# Tele.net
KiCad netlist of a schematic drawn in Altium Designer
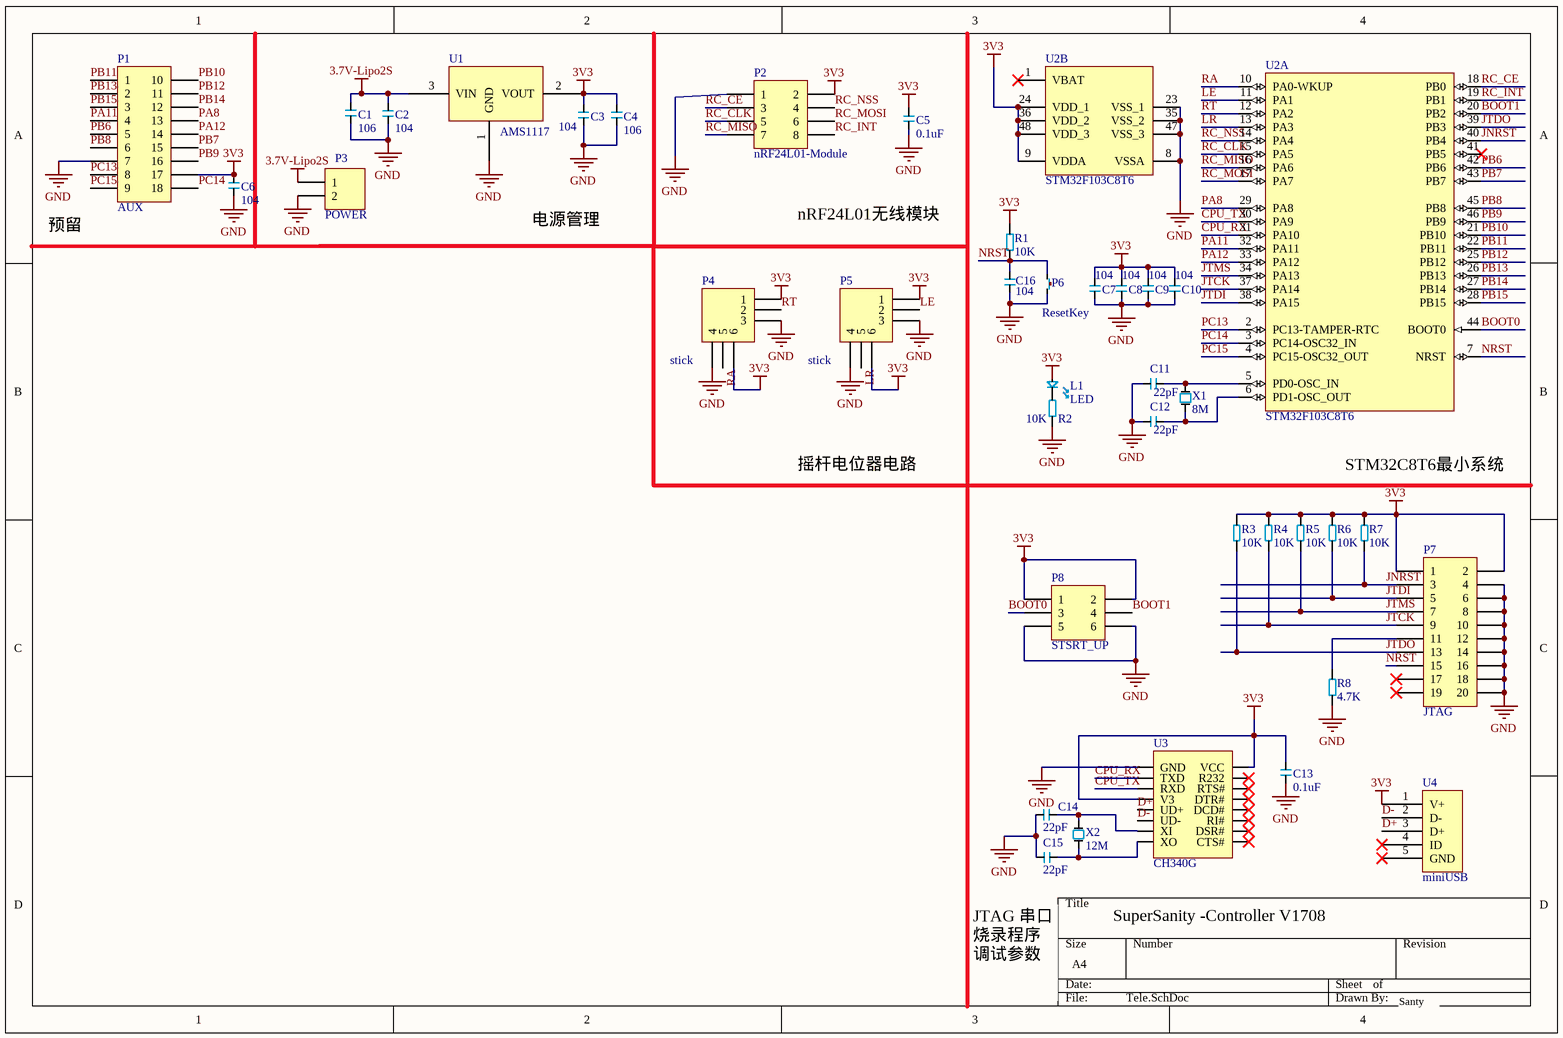
[diagram p0: Tele.SchDoc]

(export (version "E")
  (design (tool "Eeschema 10.0.6"))
  (components
    (comp (ref "C1") (value "106") (footprint "LC-0402") (libsource (lib "0402") (part "Cap-0402")))
    (comp (ref "C2") (value "104") (footprint "LC-0402") (libsource (lib "0402") (part "Cap-0402")))
    (comp (ref "C3") (value "104") (footprint "LC-0402") (libsource (lib "0402") (part "Cap-0402")))
    (comp (ref "C4") (value "106") (footprint "LC-0402") (libsource (lib "0402") (part "Cap-0402")))
    (comp (ref "C5") (value "0.1uF") (footprint "LC-0402") (libsource (lib "0402") (part "Cap-0402")))
    (comp (ref "C6") (value "104") (footprint "LC-0402") (libsource (lib "0402") (part "Cap-0402")))
    (comp (ref "C7") (value "104") (footprint "LC-0402") (libsource (lib "0402") (part "Cap-0402")))
    (comp (ref "C8") (value "104") (footprint "LC-0402") (libsource (lib "0402") (part "Cap-0402")))
    (comp (ref "C9") (value "104") (footprint "LC-0402") (libsource (lib "0402") (part "Cap-0402")))
    (comp (ref "C10") (value "104") (footprint "LC-0402") (libsource (lib "0402") (part "Cap-0402")))
    (comp (ref "C11") (value "22pF") (footprint "LC-0402") (libsource (lib "0402") (part "Cap-0402")))
    (comp (ref "C12") (value "22pF") (footprint "LC-0402") (libsource (lib "0402") (part "Cap-0402")))
    (comp (ref "C13") (value "0.1uF") (footprint "LC-0402") (libsource (lib "0402") (part "Cap-0402")))
    (comp (ref "C14") (value "22pF") (footprint "LC-0402") (libsource (lib "0402") (part "Cap-0402")))
    (comp (ref "C15") (value "22pF") (footprint "LC-0402") (libsource (lib "0402") (part "Cap-0402")))
    (comp (ref "C16") (value "104") (footprint "LC-0402") (libsource (lib "0402") (part "Cap-0402")))
    (comp (ref "L1") (value "LED") (footprint "0603_LED_S1") (libsource (lib "LED_0603") (part "LED")))
    (comp (ref "P1")
      (value "AUX")
      (footprint "HDR2X9_CEN")
      (description "Header, 9-Pin, Dual row")
      (fields (field (name "PUBLISHER") "Altium Limited"))
      (libsource (lib "Miscellaneous Connectors") (part "Header 9X2A"))
    )
    (comp (ref "P2")
      (value "nRF24L01-Module")
      (footprint "HDR2X4")
      (description "Header, 4-Pin, Dual row")
      (fields (field (name "PUBLISHER") "Altium Limited"))
      (libsource (lib "Miscellaneous Connectors") (part "Header 4X2"))
    )
    (comp (ref "P3")
      (value "POWER")
      (footprint "HDR1X2")
      (description "Header, 2-Pin")
      (fields (field (name "PUBLISHER") "Altium Limited"))
      (libsource (lib "Miscellaneous Connectors") (part "Header 2"))
    )
    (comp (ref "P4") (value "stick") (footprint "Stick") (libsource (lib "Stick") (part "stick")))
    (comp (ref "P5") (value "stick") (footprint "Stick") (libsource (lib "Stick") (part "stick")))
    (comp (ref "P6")
      (value "ResetKey")
      (footprint "ResetKeyC5382")
      (libsource (lib "ResetKey_C5382") (part "ResetKey_C5382"))
    )
    (comp (ref "P7")
      (value "JTAG")
      (footprint "HDR2X10")
      (description "Header, 10-Pin, Dual row")
      (fields (field (name "PUBLISHER") "Altium Limited"))
      (libsource (lib "Miscellaneous Connectors") (part "Header 10X2"))
    )
    (comp (ref "P8")
      (value "STSRT_UP")
      (footprint "HDR2X3")
      (description "Header, 3-Pin, Dual row")
      (fields (field (name "PUBLISHER") "Altium Limited"))
      (libsource (lib "Miscellaneous Connectors") (part "Header 3X2"))
    )
    (comp (ref "R1") (value "10K") (footprint "Res-0402") (libsource (lib "0402-Res") (part "Res-0402")))
    (comp (ref "R2") (value "10K") (footprint "Res-0402") (libsource (lib "0402-Res") (part "Res-0402")))
    (comp (ref "R3") (value "10K") (footprint "Res-0402") (libsource (lib "0402-Res") (part "Res-0402")))
    (comp (ref "R4") (value "10K") (footprint "Res-0402") (libsource (lib "0402-Res") (part "Res-0402")))
    (comp (ref "R5") (value "10K") (footprint "Res-0402") (libsource (lib "0402-Res") (part "Res-0402")))
    (comp (ref "R6") (value "10K") (footprint "Res-0402") (libsource (lib "0402-Res") (part "Res-0402")))
    (comp (ref "R7") (value "10K") (footprint "Res-0402") (libsource (lib "0402-Res") (part "Res-0402")))
    (comp (ref "R8") (value "4.7K") (footprint "Res-0402") (libsource (lib "0402-Res") (part "Res-0402")))
    (comp (ref "U1") (value "AMS1117") (footprint "AMS1117") (libsource (lib "AMS1117") (part "AMS1117")))
    (comp (ref "U2")
      (value "STM32F103C8T6")
      (footprint "STM-LQFP48_N")
      (libsource (lib "STMicroelectronics STM32 F1") (part "STM32F103C8T6"))
    )
    (comp (ref "U3")
      (value "CH340G")
      (footprint "LC-SOP-16_150mil")
      (libsource (lib "CH340G") (part "CH340G"))
    )
    (comp (ref "U4") (value "miniUSB") (footprint "miniUSB") (libsource (lib "miniUSB") (part "miniUSB")))
    (comp (ref "X1") (value "8M") (footprint "LC-HC-49SMD") (libsource (lib "49SMD-8M") (part "49SMD")))
    (comp (ref "X2") (value "12M") (footprint "LC-HC-49SMD") (libsource (lib "49SMD-8M") (part "49SMD")))
  )
  (nets
    (net (code "1") (name "/BOOT0") (class "Default")
      (node (ref "P8") (pin "3") (pinfunction "3_3") (pintype "passive"))
      (node (ref "U2") (pin "44") (pinfunction "BOOT0_44") (pintype "input"))
    )
    (net (code "2") (name "/BOOT1") (class "Default")
      (node (ref "P8") (pin "4") (pinfunction "4_4") (pintype "passive"))
      (node (ref "U2") (pin "20") (pinfunction "PB2_20") (pintype "bidirectional"))
    )
    (net (code "3") (name "/CPU_RX") (class "Default")
      (node (ref "U2") (pin "31") (pinfunction "PA10_31") (pintype "bidirectional"))
      (node (ref "U3") (pin "2") (pinfunction "TXD_2") (pintype "passive"))
    )
    (net (code "4") (name "/CPU_TX") (class "Default")
      (node (ref "U2") (pin "30") (pinfunction "PA9_30") (pintype "bidirectional"))
      (node (ref "U3") (pin "3") (pinfunction "RXD_3") (pintype "passive"))
    )
    (net (code "5") (name "/D+") (class "Default")
      (node (ref "U3") (pin "5") (pinfunction "UD+_5") (pintype "passive"))
      (node (ref "U4") (pin "3") (pinfunction "D+_3") (pintype "passive"))
    )
    (net (code "6") (name "/D-") (class "Default")
      (node (ref "U3") (pin "6") (pinfunction "UD-_6") (pintype "passive"))
      (node (ref "U4") (pin "2") (pinfunction "D-_2") (pintype "passive"))
    )
    (net (code "7") (name "/JNRST") (class "Default")
      (node (ref "P7") (pin "3") (pinfunction "3_3") (pintype "passive"))
      (node (ref "R7") (pin "1") (pinfunction "1_1") (pintype "passive"))
      (node (ref "U2") (pin "40") (pinfunction "PB4_40") (pintype "bidirectional"))
    )
    (net (code "8") (name "/JTCK") (class "Default")
      (node (ref "P7") (pin "9") (pinfunction "9_9") (pintype "passive"))
      (node (ref "R4") (pin "1") (pinfunction "1_1") (pintype "passive"))
      (node (ref "U2") (pin "37") (pinfunction "PA14_37") (pintype "bidirectional"))
    )
    (net (code "9") (name "/JTDI") (class "Default")
      (node (ref "P7") (pin "5") (pinfunction "5_5") (pintype "passive"))
      (node (ref "R6") (pin "1") (pinfunction "1_1") (pintype "passive"))
      (node (ref "U2") (pin "38") (pinfunction "PA15_38") (pintype "bidirectional"))
    )
    (net (code "10") (name "/JTDO") (class "Default")
      (node (ref "P7") (pin "13") (pinfunction "13_13") (pintype "passive"))
      (node (ref "R3") (pin "1") (pinfunction "1_1") (pintype "passive"))
      (node (ref "U2") (pin "39") (pinfunction "PB3_39") (pintype "bidirectional"))
    )
    (net (code "11") (name "/JTMS") (class "Default")
      (node (ref "P7") (pin "7") (pinfunction "7_7") (pintype "passive"))
      (node (ref "R5") (pin "1") (pinfunction "1_1") (pintype "passive"))
      (node (ref "U2") (pin "34") (pinfunction "PA13_34") (pintype "bidirectional"))
    )
    (net (code "12") (name "/LE") (class "Default")
      (node (ref "P5") (pin "2") (pinfunction "2_2") (pintype "passive"))
      (node (ref "U2") (pin "11") (pinfunction "PA1_11") (pintype "bidirectional"))
    )
    (net (code "13") (name "/LR") (class "Default")
      (node (ref "P5") (pin "5") (pinfunction "5_5") (pintype "passive"))
      (node (ref "U2") (pin "13") (pinfunction "PA3_13") (pintype "bidirectional"))
    )
    (net (code "14") (name "/NRST") (class "Default")
      (node (ref "C16") (pin "1") (pinfunction "1_1") (pintype "passive"))
      (node (ref "P6") (pin "1") (pinfunction "1_1") (pintype "passive"))
      (node (ref "P7") (pin "15") (pinfunction "15_15") (pintype "passive"))
      (node (ref "R1") (pin "1") (pinfunction "1_1") (pintype "passive"))
      (node (ref "U2") (pin "7") (pinfunction "NRST_7") (pintype "bidirectional"))
    )
    (net (code "15") (name "/PA8") (class "Default")
      (node (ref "P1") (pin "13") (pinfunction "13_13") (pintype "passive"))
      (node (ref "U2") (pin "29") (pinfunction "PA8_29") (pintype "bidirectional"))
    )
    (net (code "16") (name "/PA11") (class "Default")
      (node (ref "P1") (pin "4") (pinfunction "4_4") (pintype "passive"))
      (node (ref "U2") (pin "32") (pinfunction "PA11_32") (pintype "bidirectional"))
    )
    (net (code "17") (name "/PA12") (class "Default")
      (node (ref "P1") (pin "14") (pinfunction "14_14") (pintype "passive"))
      (node (ref "U2") (pin "33") (pinfunction "PA12_33") (pintype "bidirectional"))
    )
    (net (code "18") (name "/PB6") (class "Default")
      (node (ref "P1") (pin "5") (pinfunction "5_5") (pintype "passive"))
      (node (ref "U2") (pin "42") (pinfunction "PB6_42") (pintype "bidirectional"))
    )
    (net (code "19") (name "/PB7") (class "Default")
      (node (ref "P1") (pin "15") (pinfunction "15_15") (pintype "passive"))
      (node (ref "U2") (pin "43") (pinfunction "PB7_43") (pintype "bidirectional"))
    )
    (net (code "20") (name "/PB8") (class "Default")
      (node (ref "P1") (pin "6") (pinfunction "6_6") (pintype "passive"))
      (node (ref "U2") (pin "45") (pinfunction "PB8_45") (pintype "bidirectional"))
    )
    (net (code "21") (name "/PB9") (class "Default")
      (node (ref "P1") (pin "16") (pinfunction "16_16") (pintype "passive"))
      (node (ref "U2") (pin "46") (pinfunction "PB9_46") (pintype "bidirectional"))
    )
    (net (code "22") (name "/PB10") (class "Default")
      (node (ref "P1") (pin "10") (pinfunction "10_10") (pintype "passive"))
      (node (ref "U2") (pin "21") (pinfunction "PB10_21") (pintype "bidirectional"))
    )
    (net (code "23") (name "/PB11") (class "Default")
      (node (ref "P1") (pin "1") (pinfunction "1_1") (pintype "passive"))
      (node (ref "U2") (pin "22") (pinfunction "PB11_22") (pintype "bidirectional"))
    )
    (net (code "24") (name "/PB12") (class "Default")
      (node (ref "P1") (pin "11") (pinfunction "11_11") (pintype "passive"))
      (node (ref "U2") (pin "25") (pinfunction "PB12_25") (pintype "bidirectional"))
    )
    (net (code "25") (name "/PB13") (class "Default")
      (node (ref "P1") (pin "2") (pinfunction "2_2") (pintype "passive"))
      (node (ref "U2") (pin "26") (pinfunction "PB13_26") (pintype "bidirectional"))
    )
    (net (code "26") (name "/PB14") (class "Default")
      (node (ref "P1") (pin "12") (pinfunction "12_12") (pintype "passive"))
      (node (ref "U2") (pin "27") (pinfunction "PB14_27") (pintype "bidirectional"))
    )
    (net (code "27") (name "/PB15") (class "Default")
      (node (ref "P1") (pin "3") (pinfunction "3_3") (pintype "passive"))
      (node (ref "U2") (pin "28") (pinfunction "PB15_28") (pintype "bidirectional"))
    )
    (net (code "28") (name "/PC13") (class "Default")
      (node (ref "P1") (pin "8") (pinfunction "8_8") (pintype "passive"))
      (node (ref "U2") (pin "2") (pinfunction "PC13-TAMPER-RTC_2") (pintype "bidirectional"))
    )
    (net (code "29") (name "/PC14") (class "Default")
      (node (ref "P1") (pin "18") (pinfunction "18_18") (pintype "passive"))
      (node (ref "U2") (pin "3") (pinfunction "PC14-OSC32_IN_3") (pintype "bidirectional"))
    )
    (net (code "30") (name "/PC15") (class "Default")
      (node (ref "P1") (pin "9") (pinfunction "9_9") (pintype "passive"))
      (node (ref "U2") (pin "4") (pinfunction "PC15-OSC32_OUT_4") (pintype "bidirectional"))
    )
    (net (code "31") (name "/RA") (class "Default")
      (node (ref "P4") (pin "5") (pinfunction "5_5") (pintype "passive"))
      (node (ref "U2") (pin "10") (pinfunction "PA0-WKUP_10") (pintype "bidirectional"))
    )
    (net (code "32") (name "/RC_CE") (class "Default")
      (node (ref "P2") (pin "3") (pinfunction "3_3") (pintype "passive"))
      (node (ref "U2") (pin "18") (pinfunction "PB0_18") (pintype "bidirectional"))
    )
    (net (code "33") (name "/RC_CLK") (class "Default")
      (node (ref "P2") (pin "5") (pinfunction "5_5") (pintype "passive"))
      (node (ref "U2") (pin "15") (pinfunction "PA5_15") (pintype "bidirectional"))
    )
    (net (code "34") (name "/RC_INT") (class "Default")
      (node (ref "P2") (pin "8") (pinfunction "8_8") (pintype "passive"))
      (node (ref "U2") (pin "19") (pinfunction "PB1_19") (pintype "bidirectional"))
    )
    (net (code "35") (name "/RC_MISO") (class "Default")
      (node (ref "P2") (pin "7") (pinfunction "7_7") (pintype "passive"))
      (node (ref "U2") (pin "16") (pinfunction "PA6_16") (pintype "bidirectional"))
    )
    (net (code "36") (name "/RC_MOSI") (class "Default")
      (node (ref "P2") (pin "6") (pinfunction "6_6") (pintype "passive"))
      (node (ref "U2") (pin "17") (pinfunction "PA7_17") (pintype "bidirectional"))
    )
    (net (code "37") (name "/RC_NSS") (class "Default")
      (node (ref "P2") (pin "4") (pinfunction "4_4") (pintype "passive"))
      (node (ref "U2") (pin "14") (pinfunction "PA4_14") (pintype "bidirectional"))
    )
    (net (code "38") (name "/RT") (class "Default")
      (node (ref "P4") (pin "2") (pinfunction "2_2") (pintype "passive"))
      (node (ref "U2") (pin "12") (pinfunction "PA2_12") (pintype "bidirectional"))
    )
    (net (code "39") (name "3.7V-Lipo2S") (class "Default")
      (node (ref "C1") (pin "1") (pinfunction "1_1") (pintype "passive"))
      (node (ref "C2") (pin "1") (pinfunction "1_1") (pintype "passive"))
      (node (ref "P3") (pin "1") (pinfunction "1_1") (pintype "passive"))
      (node (ref "U1") (pin "3") (pinfunction "VIN_3") (pintype "passive"))
    )
    (net (code "40") (name "3V3") (class "Default")
      (node (ref "C10") (pin "1") (pinfunction "1_1") (pintype "passive"))
      (node (ref "C13") (pin "1") (pinfunction "1_1") (pintype "passive"))
      (node (ref "C3") (pin "1") (pinfunction "1_1") (pintype "passive"))
      (node (ref "C4") (pin "1") (pinfunction "1_1") (pintype "passive"))
      (node (ref "C5") (pin "1") (pinfunction "1_1") (pintype "passive"))
      (node (ref "C6") (pin "1") (pinfunction "1_1") (pintype "passive"))
      (node (ref "C7") (pin "1") (pinfunction "1_1") (pintype "passive"))
      (node (ref "C8") (pin "1") (pinfunction "1_1") (pintype "passive"))
      (node (ref "C9") (pin "1") (pinfunction "1_1") (pintype "passive"))
      (node (ref "L1") (pin "P") (pinfunction "1_P") (pintype "passive"))
      (node (ref "P1") (pin "17") (pinfunction "17_17") (pintype "passive"))
      (node (ref "P2") (pin "2") (pinfunction "2_2") (pintype "passive"))
      (node (ref "P4") (pin "1") (pinfunction "1_1") (pintype "passive"))
      (node (ref "P4") (pin "6") (pinfunction "6_6") (pintype "passive"))
      (node (ref "P5") (pin "1") (pinfunction "1_1") (pintype "passive"))
      (node (ref "P5") (pin "6") (pinfunction "6_6") (pintype "passive"))
      (node (ref "P7") (pin "1") (pinfunction "1_1") (pintype "passive"))
      (node (ref "P7") (pin "2") (pinfunction "2_2") (pintype "passive"))
      (node (ref "P8") (pin "1") (pinfunction "1_1") (pintype "passive"))
      (node (ref "P8") (pin "2") (pinfunction "2_2") (pintype "passive"))
      (node (ref "R1") (pin "0") (pinfunction "0_0") (pintype "passive"))
      (node (ref "R3") (pin "0") (pinfunction "0_0") (pintype "passive"))
      (node (ref "R4") (pin "0") (pinfunction "0_0") (pintype "passive"))
      (node (ref "R5") (pin "0") (pinfunction "0_0") (pintype "passive"))
      (node (ref "R6") (pin "0") (pinfunction "0_0") (pintype "passive"))
      (node (ref "R7") (pin "0") (pinfunction "0_0") (pintype "passive"))
      (node (ref "U1") (pin "2") (pinfunction "VOUT_2") (pintype "passive"))
      (node (ref "U2") (pin "24") (pinfunction "VDD_1_24") (pintype "power_in"))
      (node (ref "U2") (pin "36") (pinfunction "VDD_2_36") (pintype "power_in"))
      (node (ref "U2") (pin "48") (pinfunction "VDD_3_48") (pintype "power_in"))
      (node (ref "U2") (pin "9") (pinfunction "VDDA_9") (pintype "power_in"))
      (node (ref "U3") (pin "16") (pinfunction "VCC_16") (pintype "passive"))
      (node (ref "U3") (pin "4") (pinfunction "V3_4") (pintype "passive"))
      (node (ref "U4") (pin "1") (pinfunction "V+_1") (pintype "passive"))
    )
    (net (code "41") (name "GND") (class "Default")
      (node (ref "C1") (pin "0") (pinfunction "0_0") (pintype "passive"))
      (node (ref "C10") (pin "0") (pinfunction "0_0") (pintype "passive"))
      (node (ref "C11") (pin "0") (pinfunction "0_0") (pintype "passive"))
      (node (ref "C12") (pin "0") (pinfunction "0_0") (pintype "passive"))
      (node (ref "C13") (pin "0") (pinfunction "0_0") (pintype "passive"))
      (node (ref "C14") (pin "0") (pinfunction "0_0") (pintype "passive"))
      (node (ref "C15") (pin "0") (pinfunction "0_0") (pintype "passive"))
      (node (ref "C16") (pin "0") (pinfunction "0_0") (pintype "passive"))
      (node (ref "C2") (pin "0") (pinfunction "0_0") (pintype "passive"))
      (node (ref "C3") (pin "0") (pinfunction "0_0") (pintype "passive"))
      (node (ref "C4") (pin "0") (pinfunction "0_0") (pintype "passive"))
      (node (ref "C5") (pin "0") (pinfunction "0_0") (pintype "passive"))
      (node (ref "C6") (pin "0") (pinfunction "0_0") (pintype "passive"))
      (node (ref "C7") (pin "0") (pinfunction "0_0") (pintype "passive"))
      (node (ref "C8") (pin "0") (pinfunction "0_0") (pintype "passive"))
      (node (ref "C9") (pin "0") (pinfunction "0_0") (pintype "passive"))
      (node (ref "P1") (pin "7") (pinfunction "7_7") (pintype "passive"))
      (node (ref "P2") (pin "1") (pinfunction "1_1") (pintype "passive"))
      (node (ref "P3") (pin "2") (pinfunction "2_2") (pintype "passive"))
      (node (ref "P4") (pin "3") (pinfunction "3_3") (pintype "passive"))
      (node (ref "P4") (pin "4") (pinfunction "4_4") (pintype "passive"))
      (node (ref "P5") (pin "3") (pinfunction "3_3") (pintype "passive"))
      (node (ref "P5") (pin "4") (pinfunction "4_4") (pintype "passive"))
      (node (ref "P6") (pin "0") (pinfunction "0_0") (pintype "passive"))
      (node (ref "P7") (pin "10") (pinfunction "10_10") (pintype "passive"))
      (node (ref "P7") (pin "12") (pinfunction "12_12") (pintype "passive"))
      (node (ref "P7") (pin "14") (pinfunction "14_14") (pintype "passive"))
      (node (ref "P7") (pin "16") (pinfunction "16_16") (pintype "passive"))
      (node (ref "P7") (pin "18") (pinfunction "18_18") (pintype "passive"))
      (node (ref "P7") (pin "20") (pinfunction "20_20") (pintype "passive"))
      (node (ref "P7") (pin "4") (pinfunction "4_4") (pintype "passive"))
      (node (ref "P7") (pin "6") (pinfunction "6_6") (pintype "passive"))
      (node (ref "P7") (pin "8") (pinfunction "8_8") (pintype "passive"))
      (node (ref "P8") (pin "5") (pinfunction "5_5") (pintype "passive"))
      (node (ref "P8") (pin "6") (pinfunction "6_6") (pintype "passive"))
      (node (ref "R2") (pin "1") (pinfunction "1_1") (pintype "passive"))
      (node (ref "R8") (pin "1") (pinfunction "1_1") (pintype "passive"))
      (node (ref "U1") (pin "1") (pinfunction "GND_1") (pintype "passive"))
      (node (ref "U2") (pin "23") (pinfunction "VSS_1_23") (pintype "power_in"))
      (node (ref "U2") (pin "35") (pinfunction "VSS_2_35") (pintype "power_in"))
      (node (ref "U2") (pin "47") (pinfunction "VSS_3_47") (pintype "power_in"))
      (node (ref "U2") (pin "8") (pinfunction "VSSA_8") (pintype "power_in"))
      (node (ref "U3") (pin "1") (pinfunction "GND_1") (pintype "passive"))
    )
    (net (code "42") (name "Net-(L1-2)") (class "Default")
      (node (ref "L1") (pin "N") (pinfunction "2_N") (pintype "passive"))
      (node (ref "R2") (pin "0") (pinfunction "0_0") (pintype "passive"))
    )
    (net (code "43") (name "Net-(P7-Pad11)") (class "Default")
      (node (ref "P7") (pin "11") (pinfunction "11_11") (pintype "passive"))
      (node (ref "R8") (pin "0") (pinfunction "0_0") (pintype "passive"))
    )
    (net (code "44") (name "Net-(U2A-PD0-OSC_IN)") (class "Default")
      (node (ref "C11") (pin "1") (pinfunction "1_1") (pintype "passive"))
      (node (ref "U2") (pin "5") (pinfunction "PD0-OSC_IN_5") (pintype "bidirectional"))
      (node (ref "X1") (pin "0") (pinfunction "0_0") (pintype "passive"))
    )
    (net (code "45") (name "Net-(U2A-PD1-OSC_OUT)") (class "Default")
      (node (ref "C12") (pin "1") (pinfunction "1_1") (pintype "passive"))
      (node (ref "U2") (pin "6") (pinfunction "PD1-OSC_OUT_6") (pintype "bidirectional"))
      (node (ref "X1") (pin "1") (pinfunction "1_1") (pintype "passive"))
    )
    (net (code "46") (name "Net-(U3-XI)") (class "Default")
      (node (ref "C14") (pin "1") (pinfunction "1_1") (pintype "passive"))
      (node (ref "U3") (pin "7") (pinfunction "XI_7") (pintype "passive"))
      (node (ref "X2") (pin "0") (pinfunction "0_0") (pintype "passive"))
    )
    (net (code "47") (name "Net-(U3-XO)") (class "Default")
      (node (ref "C15") (pin "1") (pinfunction "1_1") (pintype "passive"))
      (node (ref "U3") (pin "8") (pinfunction "XO_8") (pintype "passive"))
      (node (ref "X2") (pin "1") (pinfunction "1_1") (pintype "passive"))
    )
    (net (code "48") (name "unconnected-(P7-Pad17)") (class "Default")
      (node (ref "P7") (pin "17") (pinfunction "17_17") (pintype "passive+no_connect"))
    )
    (net (code "49") (name "unconnected-(P7-Pad19)") (class "Default")
      (node (ref "P7") (pin "19") (pinfunction "19_19") (pintype "passive+no_connect"))
    )
    (net (code "50") (name "unconnected-(U2A-PB5-Pad41)") (class "Default")
      (node (ref "U2") (pin "41") (pinfunction "PB5_41") (pintype "bidirectional+no_connect"))
    )
    (net (code "51") (name "unconnected-(U2B-VBAT-Pad1)") (class "Default")
      (node (ref "U2") (pin "1") (pinfunction "VBAT_1") (pintype "power_in+no_connect"))
    )
    (net (code "52") (name "unconnected-(U3-CTS#-Pad9)") (class "Default")
      (node (ref "U3") (pin "9") (pinfunction "CTS#_9") (pintype "passive+no_connect"))
    )
    (net (code "53") (name "unconnected-(U3-DCD#-Pad12)") (class "Default")
      (node (ref "U3") (pin "12") (pinfunction "DCD#_12") (pintype "passive+no_connect"))
    )
    (net (code "54") (name "unconnected-(U3-DSR#-Pad10)") (class "Default")
      (node (ref "U3") (pin "10") (pinfunction "DSR#_10") (pintype "passive+no_connect"))
    )
    (net (code "55") (name "unconnected-(U3-DTR#-Pad13)") (class "Default")
      (node (ref "U3") (pin "13") (pinfunction "DTR#_13") (pintype "passive+no_connect"))
    )
    (net (code "56") (name "unconnected-(U3-R232-Pad15)") (class "Default")
      (node (ref "U3") (pin "15") (pinfunction "R232_15") (pintype "passive+no_connect"))
    )
    (net (code "57") (name "unconnected-(U3-RI#-Pad11)") (class "Default")
      (node (ref "U3") (pin "11") (pinfunction "RI#_11") (pintype "passive+no_connect"))
    )
    (net (code "58") (name "unconnected-(U3-RTS#-Pad14)") (class "Default")
      (node (ref "U3") (pin "14") (pinfunction "RTS#_14") (pintype "passive+no_connect"))
    )
    (net (code "59") (name "unconnected-(U4-GND-Pad5)") (class "Default")
      (node (ref "U4") (pin "5") (pinfunction "GND_5") (pintype "passive+no_connect"))
    )
    (net (code "60") (name "unconnected-(U4-ID-Pad4)") (class "Default")
      (node (ref "U4") (pin "4") (pinfunction "ID_4") (pintype "passive+no_connect"))
    )
  )
)
